# tetris_bigger.net
KiCad netlist of a schematic drawn in EAGLE
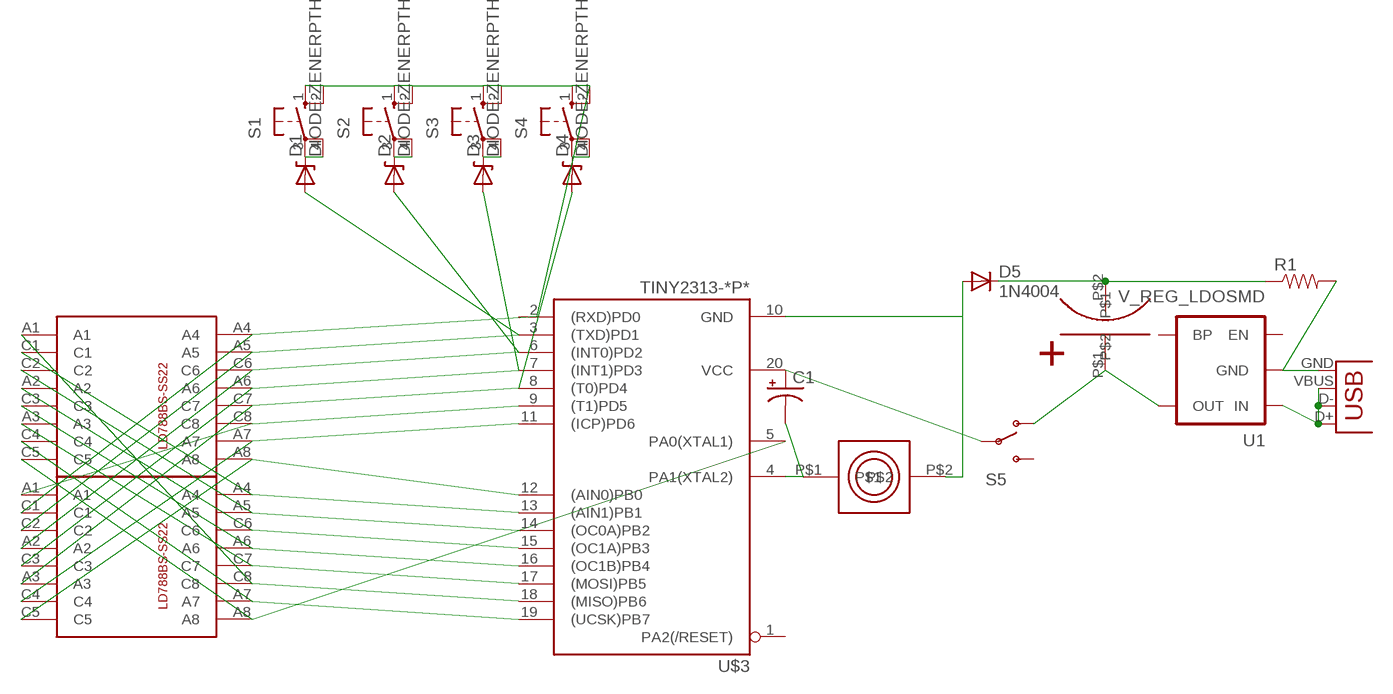
[diagram p0: schematic, sheet 1]

(export (version "E")
  (design (tool "Eeschema 10.0.6"))
  (components
    (comp (ref "C1")
      (value "CAP_POLPTH1")
      (footprint "eagle-import:CPOL-RADIAL-100UF-25V")
      (libsource (lib "eagle-import") (part "CAP_POLPTH1"))
    )
    (comp (ref "D1")
      (value "DIODE-ZENERPTH")
      (footprint "eagle-import:DIODE-ZENER")
      (libsource (lib "eagle-import") (part "DIODE-ZENERPTH"))
    )
    (comp (ref "D2")
      (value "DIODE-ZENERPTH")
      (footprint "eagle-import:DIODE-ZENER")
      (libsource (lib "eagle-import") (part "DIODE-ZENERPTH"))
    )
    (comp (ref "D3")
      (value "DIODE-ZENERPTH")
      (footprint "eagle-import:DIODE-ZENER")
      (libsource (lib "eagle-import") (part "DIODE-ZENERPTH"))
    )
    (comp (ref "D4")
      (value "DIODE-ZENERPTH")
      (footprint "eagle-import:DIODE-ZENER")
      (libsource (lib "eagle-import") (part "DIODE-ZENERPTH"))
    )
    (comp (ref "D5")
      (value "1N4004")
      (footprint "eagle-import:DO41-10")
      (libsource (lib "eagle-import") (part "1N4004"))
    )
    (comp (ref "R1")
      (value "RESISTORPTH1")
      (footprint "eagle-import:AXIAL-0.3")
      (libsource (lib "eagle-import") (part "RESISTORPTH1"))
    )
    (comp (ref "S1")
      (value "10-XX")
      (footprint "eagle-import:B3F-10XX")
      (fields (field (name "MPN") "B3F-1000"))
      (libsource (lib "eagle-import") (part "10-XX"))
    )
    (comp (ref "S2")
      (value "10-XX")
      (footprint "eagle-import:B3F-10XX")
      (fields (field (name "MPN") "B3F-1000"))
      (libsource (lib "eagle-import") (part "10-XX"))
    )
    (comp (ref "S3")
      (value "10-XX")
      (footprint "eagle-import:B3F-10XX")
      (fields (field (name "MPN") "B3F-1000"))
      (libsource (lib "eagle-import") (part "10-XX"))
    )
    (comp (ref "S4")
      (value "10-XX")
      (footprint "eagle-import:B3F-10XX")
      (fields (field (name "MPN") "B3F-1000"))
      (libsource (lib "eagle-import") (part "10-XX"))
    )
    (comp (ref "S5")
      (value "SWITCH-SPSTSMD2")
      (footprint "eagle-import:SWITCH-SPDT-SMD")
      (libsource (lib "eagle-import") (part "SWITCH-SPSTSMD2"))
    )
    (comp (ref "U$1")
      (value "LD-1088BS")
      (footprint "eagle-import:LD-1088BS")
      (libsource (lib "eagle-import") (part "LD-1088BS"))
    )
    (comp (ref "U$2")
      (value "LD-1088BS")
      (footprint "eagle-import:LD-1088BS")
      (libsource (lib "eagle-import") (part "LD-1088BS"))
    )
    (comp (ref "U$3")
      (value "TINY2313-*P*")
      (footprint "eagle-import:DIL20")
      (libsource (lib "eagle-import") (part "TINY2313-P"))
    )
    (comp (ref "U$4")
      (value "I-80450RF")
      (footprint "eagle-import:ISK4.1K_I-80450RF_I2G")
      (libsource (lib "eagle-import") (part "I-80450RF"))
    )
    (comp (ref "U$5")
      (value "NICHICON_12F")
      (footprint "eagle-import:NICHICON_10X30")
      (libsource (lib "eagle-import") (part "NICHICON_12F"))
    )
    (comp (ref "U1")
      (value "V_REG_LDOSMD")
      (footprint "eagle-import:SOT23-5")
      (libsource (lib "eagle-import") (part "V_REG_LDOSMD"))
    )
    (comp (ref "X1")
      (value "USB-MICROB")
      (footprint "eagle-import:USB-MICROB")
      (libsource (lib "eagle-import") (part "USB-MICROB"))
    )
  )
  (nets
    (net (code "1") (name "Net-(C1-+)") (class "Default")
      (node (ref "C1") (pin "1") (pinfunction "+_1") (pintype "passive"))
      (node (ref "S5") (pin "2") (pinfunction "P_2") (pintype "passive"))
      (node (ref "U$3") (pin "20") (pinfunction "VCC_20") (pintype "power_in"))
    )
    (net (code "2") (name "Net-(C1--)") (class "Default")
      (node (ref "C1") (pin "2") (pinfunction "-_2") (pintype "passive"))
      (node (ref "U$3") (pin "4") (pinfunction "PA1(XTAL2)_4") (pintype "bidirectional"))
      (node (ref "U$4") (pin "P$1") (pinfunction "P$1_P$1") (pintype "bidirectional"))
    )
    (net (code "3") (name "Net-(D1-A)") (class "Default")
      (node (ref "D1") (pin "P$2") (pinfunction "A_P$2") (pintype "passive"))
      (node (ref "U$1") (pin "C2") (pinfunction "C2_C2") (pintype "bidirectional"))
      (node (ref "U$2") (pin "A5") (pinfunction "A5_A5") (pintype "bidirectional"))
      (node (ref "U$3") (pin "3") (pinfunction "(TXD)PD1_3") (pintype "bidirectional"))
    )
    (net (code "4") (name "Net-(D1-C)") (class "Default")
      (node (ref "D1") (pin "P$1") (pinfunction "C_P$1") (pintype "passive"))
      (node (ref "S1") (pin "3") (pinfunction "P_3") (pintype "passive"))
      (node (ref "S1") (pin "4") (pinfunction "P1_4") (pintype "passive"))
    )
    (net (code "5") (name "Net-(D2-A)") (class "Default")
      (node (ref "D2") (pin "P$2") (pinfunction "A_P$2") (pintype "passive"))
      (node (ref "U$1") (pin "A2") (pinfunction "A2_A2") (pintype "bidirectional"))
      (node (ref "U$2") (pin "C6") (pinfunction "C6_C6") (pintype "bidirectional"))
      (node (ref "U$3") (pin "6") (pinfunction "(INT0)PD2_6") (pintype "bidirectional"))
    )
    (net (code "6") (name "Net-(D2-C)") (class "Default")
      (node (ref "D2") (pin "P$1") (pinfunction "C_P$1") (pintype "passive"))
      (node (ref "S2") (pin "3") (pinfunction "P_3") (pintype "passive"))
      (node (ref "S2") (pin "4") (pinfunction "P1_4") (pintype "passive"))
    )
    (net (code "7") (name "Net-(D3-A)") (class "Default")
      (node (ref "D3") (pin "P$2") (pinfunction "A_P$2") (pintype "passive"))
      (node (ref "U$1") (pin "C3") (pinfunction "C3_C3") (pintype "bidirectional"))
      (node (ref "U$2") (pin "A6") (pinfunction "A6_A6") (pintype "bidirectional"))
      (node (ref "U$3") (pin "7") (pinfunction "(INT1)PD3_7") (pintype "bidirectional"))
    )
    (net (code "8") (name "Net-(D3-C)") (class "Default")
      (node (ref "D3") (pin "P$1") (pinfunction "C_P$1") (pintype "passive"))
      (node (ref "S3") (pin "3") (pinfunction "P_3") (pintype "passive"))
      (node (ref "S3") (pin "4") (pinfunction "P1_4") (pintype "passive"))
    )
    (net (code "9") (name "Net-(D4-A)") (class "Default")
      (node (ref "D4") (pin "P$2") (pinfunction "A_P$2") (pintype "passive"))
      (node (ref "U$1") (pin "A3") (pinfunction "A3_A3") (pintype "bidirectional"))
      (node (ref "U$2") (pin "C7") (pinfunction "C7_C7") (pintype "bidirectional"))
      (node (ref "U$3") (pin "8") (pinfunction "(T0)PD4_8") (pintype "bidirectional"))
    )
    (net (code "10") (name "Net-(D4-C)") (class "Default")
      (node (ref "D4") (pin "P$1") (pinfunction "C_P$1") (pintype "passive"))
      (node (ref "S4") (pin "3") (pinfunction "P_3") (pintype "passive"))
      (node (ref "S4") (pin "4") (pinfunction "P1_4") (pintype "passive"))
    )
    (net (code "11") (name "Net-(R1-1)") (class "Default")
      (node (ref "D5") (pin "C") (pinfunction "C_C") (pintype "passive"))
      (node (ref "R1") (pin "P$1") (pinfunction "1_P$1") (pintype "passive"))
      (node (ref "U$5") (pin "P$2") (pinfunction "P$2_P$2") (pintype "bidirectional"))
    )
    (net (code "12") (name "Net-(R1-2)") (class "Default")
      (node (ref "R1") (pin "P$2") (pinfunction "2_P$2") (pintype "passive"))
      (node (ref "U1") (pin "2") (pinfunction "GND_2") (pintype "input"))
      (node (ref "X1") (pin "GND") (pinfunction "GND_GND") (pintype "bidirectional"))
    )
    (net (code "13") (name "Net-(S1-S)") (class "Default")
      (node (ref "S1") (pin "1") (pinfunction "S_1") (pintype "passive"))
      (node (ref "S1") (pin "2") (pinfunction "S1_2") (pintype "passive"))
      (node (ref "S2") (pin "1") (pinfunction "S_1") (pintype "passive"))
      (node (ref "S2") (pin "2") (pinfunction "S1_2") (pintype "passive"))
      (node (ref "S3") (pin "1") (pinfunction "S_1") (pintype "passive"))
      (node (ref "S3") (pin "2") (pinfunction "S1_2") (pintype "passive"))
      (node (ref "S4") (pin "1") (pinfunction "S_1") (pintype "passive"))
      (node (ref "S4") (pin "2") (pinfunction "S1_2") (pintype "passive"))
      (node (ref "U$1") (pin "C1") (pinfunction "C1_C1") (pintype "bidirectional"))
      (node (ref "U$2") (pin "A4") (pinfunction "A4_A4") (pintype "bidirectional"))
    )
    (net (code "14") (name "Net-(S5-O)") (class "Default")
      (node (ref "S5") (pin "1") (pinfunction "O_1") (pintype "passive"))
      (node (ref "U$5") (pin "P$1") (pinfunction "P$1_P$1") (pintype "bidirectional"))
      (node (ref "U1") (pin "5") (pinfunction "OUT_5") (pintype "passive"))
    )
    (net (code "15") (name "Net-(U$3-(AIN0)PB0)") (class "Default")
      (node (ref "U$1") (pin "C5") (pinfunction "C5_C5") (pintype "bidirectional"))
      (node (ref "U$2") (pin "A8") (pinfunction "A8_A8") (pintype "bidirectional"))
      (node (ref "U$3") (pin "12") (pinfunction "(AIN0)PB0_12") (pintype "bidirectional"))
    )
    (net (code "16") (name "Net-(U$3-(AIN1)PB1)") (class "Default")
      (node (ref "U$1") (pin "A4") (pinfunction "A4_A4") (pintype "bidirectional"))
      (node (ref "U$2") (pin "C1") (pinfunction "C1_C1") (pintype "bidirectional"))
      (node (ref "U$3") (pin "13") (pinfunction "(AIN1)PB1_13") (pintype "bidirectional"))
    )
    (net (code "17") (name "Net-(U$3-(ICP)PD6)") (class "Default")
      (node (ref "U$1") (pin "C4") (pinfunction "C4_C4") (pintype "bidirectional"))
      (node (ref "U$2") (pin "A7") (pinfunction "A7_A7") (pintype "bidirectional"))
      (node (ref "U$3") (pin "11") (pinfunction "(ICP)PD6_11") (pintype "bidirectional"))
    )
    (net (code "18") (name "Net-(U$3-(MISO)PB6)") (class "Default")
      (node (ref "U$1") (pin "C8") (pinfunction "C8_C8") (pintype "bidirectional"))
      (node (ref "U$2") (pin "A1") (pinfunction "A1_A1") (pintype "bidirectional"))
      (node (ref "U$3") (pin "18") (pinfunction "(MISO)PB6_18") (pintype "bidirectional"))
    )
    (net (code "19") (name "Net-(U$3-(MOSI)PB5)") (class "Default")
      (node (ref "U$1") (pin "C7") (pinfunction "C7_C7") (pintype "bidirectional"))
      (node (ref "U$2") (pin "A3") (pinfunction "A3_A3") (pintype "bidirectional"))
      (node (ref "U$3") (pin "17") (pinfunction "(MOSI)PB5_17") (pintype "bidirectional"))
    )
    (net (code "20") (name "Net-(U$3-(OC0A)PB2)") (class "Default")
      (node (ref "U$1") (pin "A5") (pinfunction "A5_A5") (pintype "bidirectional"))
      (node (ref "U$2") (pin "C2") (pinfunction "C2_C2") (pintype "bidirectional"))
      (node (ref "U$3") (pin "14") (pinfunction "(OC0A)PB2_14") (pintype "bidirectional"))
    )
    (net (code "21") (name "Net-(U$3-(OC1A)PB3)") (class "Default")
      (node (ref "U$1") (pin "C6") (pinfunction "C6_C6") (pintype "bidirectional"))
      (node (ref "U$2") (pin "A2") (pinfunction "A2_A2") (pintype "bidirectional"))
      (node (ref "U$3") (pin "15") (pinfunction "(OC1A)PB3_15") (pintype "bidirectional"))
    )
    (net (code "22") (name "Net-(U$3-(OC1B)PB4)") (class "Default")
      (node (ref "U$1") (pin "A6") (pinfunction "A6_A6") (pintype "bidirectional"))
      (node (ref "U$2") (pin "C3") (pinfunction "C3_C3") (pintype "bidirectional"))
      (node (ref "U$3") (pin "16") (pinfunction "(OC1B)PB4_16") (pintype "bidirectional"))
    )
    (net (code "23") (name "Net-(U$3-(T1)PD5)") (class "Default")
      (node (ref "U$1") (pin "A1") (pinfunction "A1_A1") (pintype "bidirectional"))
      (node (ref "U$2") (pin "C8") (pinfunction "C8_C8") (pintype "bidirectional"))
      (node (ref "U$3") (pin "9") (pinfunction "(T1)PD5_9") (pintype "bidirectional"))
    )
    (net (code "24") (name "Net-(U$3-(UCSK)PB7)") (class "Default")
      (node (ref "U$1") (pin "A7") (pinfunction "A7_A7") (pintype "bidirectional"))
      (node (ref "U$2") (pin "C4") (pinfunction "C4_C4") (pintype "bidirectional"))
      (node (ref "U$3") (pin "19") (pinfunction "(UCSK)PB7_19") (pintype "bidirectional"))
    )
    (net (code "25") (name "Net-(U$3-GND)") (class "Default")
      (node (ref "D5") (pin "A") (pinfunction "A_A") (pintype "passive"))
      (node (ref "U$3") (pin "10") (pinfunction "GND_10") (pintype "power_in"))
      (node (ref "U$4") (pin "P$2") (pinfunction "P$2_P$2") (pintype "bidirectional"))
    )
    (net (code "26") (name "Net-(U$3-PA0(XTAL1))") (class "Default")
      (node (ref "U$1") (pin "A8") (pinfunction "A8_A8") (pintype "bidirectional"))
      (node (ref "U$2") (pin "C5") (pinfunction "C5_C5") (pintype "bidirectional"))
      (node (ref "U$3") (pin "5") (pinfunction "PA0(XTAL1)_5") (pintype "bidirectional"))
    )
    (net (code "27") (name "Net-(U1-IN)") (class "Default")
      (node (ref "U1") (pin "1") (pinfunction "IN_1") (pintype "input"))
      (node (ref "X1") (pin "D+") (pinfunction "D+_D+") (pintype "bidirectional"))
      (node (ref "X1") (pin "D-") (pinfunction "D-_D-") (pintype "bidirectional"))
      (node (ref "X1") (pin "VBUS") (pinfunction "VBUS_VBUS") (pintype "bidirectional"))
    )
    (net (code "28") (name "unconnected-(S5-S-Pad3)") (class "Default")
      (node (ref "S5") (pin "3") (pinfunction "S_3") (pintype "passive"))
    )
    (net (code "29") (name "unconnected-(U$3-(RXD)PD0-Pad2)") (class "Default")
      (node (ref "U$3") (pin "2") (pinfunction "(RXD)PD0_2") (pintype "bidirectional"))
    )
    (net (code "30") (name "unconnected-(U$3-PA2({slash}RESET)-Pad1)") (class "Default")
      (node (ref "U$3") (pin "1") (pinfunction "PA2(/RESET)_1") (pintype "input"))
    )
    (net (code "31") (name "unconnected-(U1-BP-Pad4)") (class "Default")
      (node (ref "U1") (pin "4") (pinfunction "BP_4") (pintype "input"))
    )
    (net (code "32") (name "unconnected-(U1-EN-Pad3)") (class "Default")
      (node (ref "U1") (pin "3") (pinfunction "EN_3") (pintype "input"))
    )
  )
)
